# MCU.net
KiCad netlist of a schematic drawn in Altium Designer
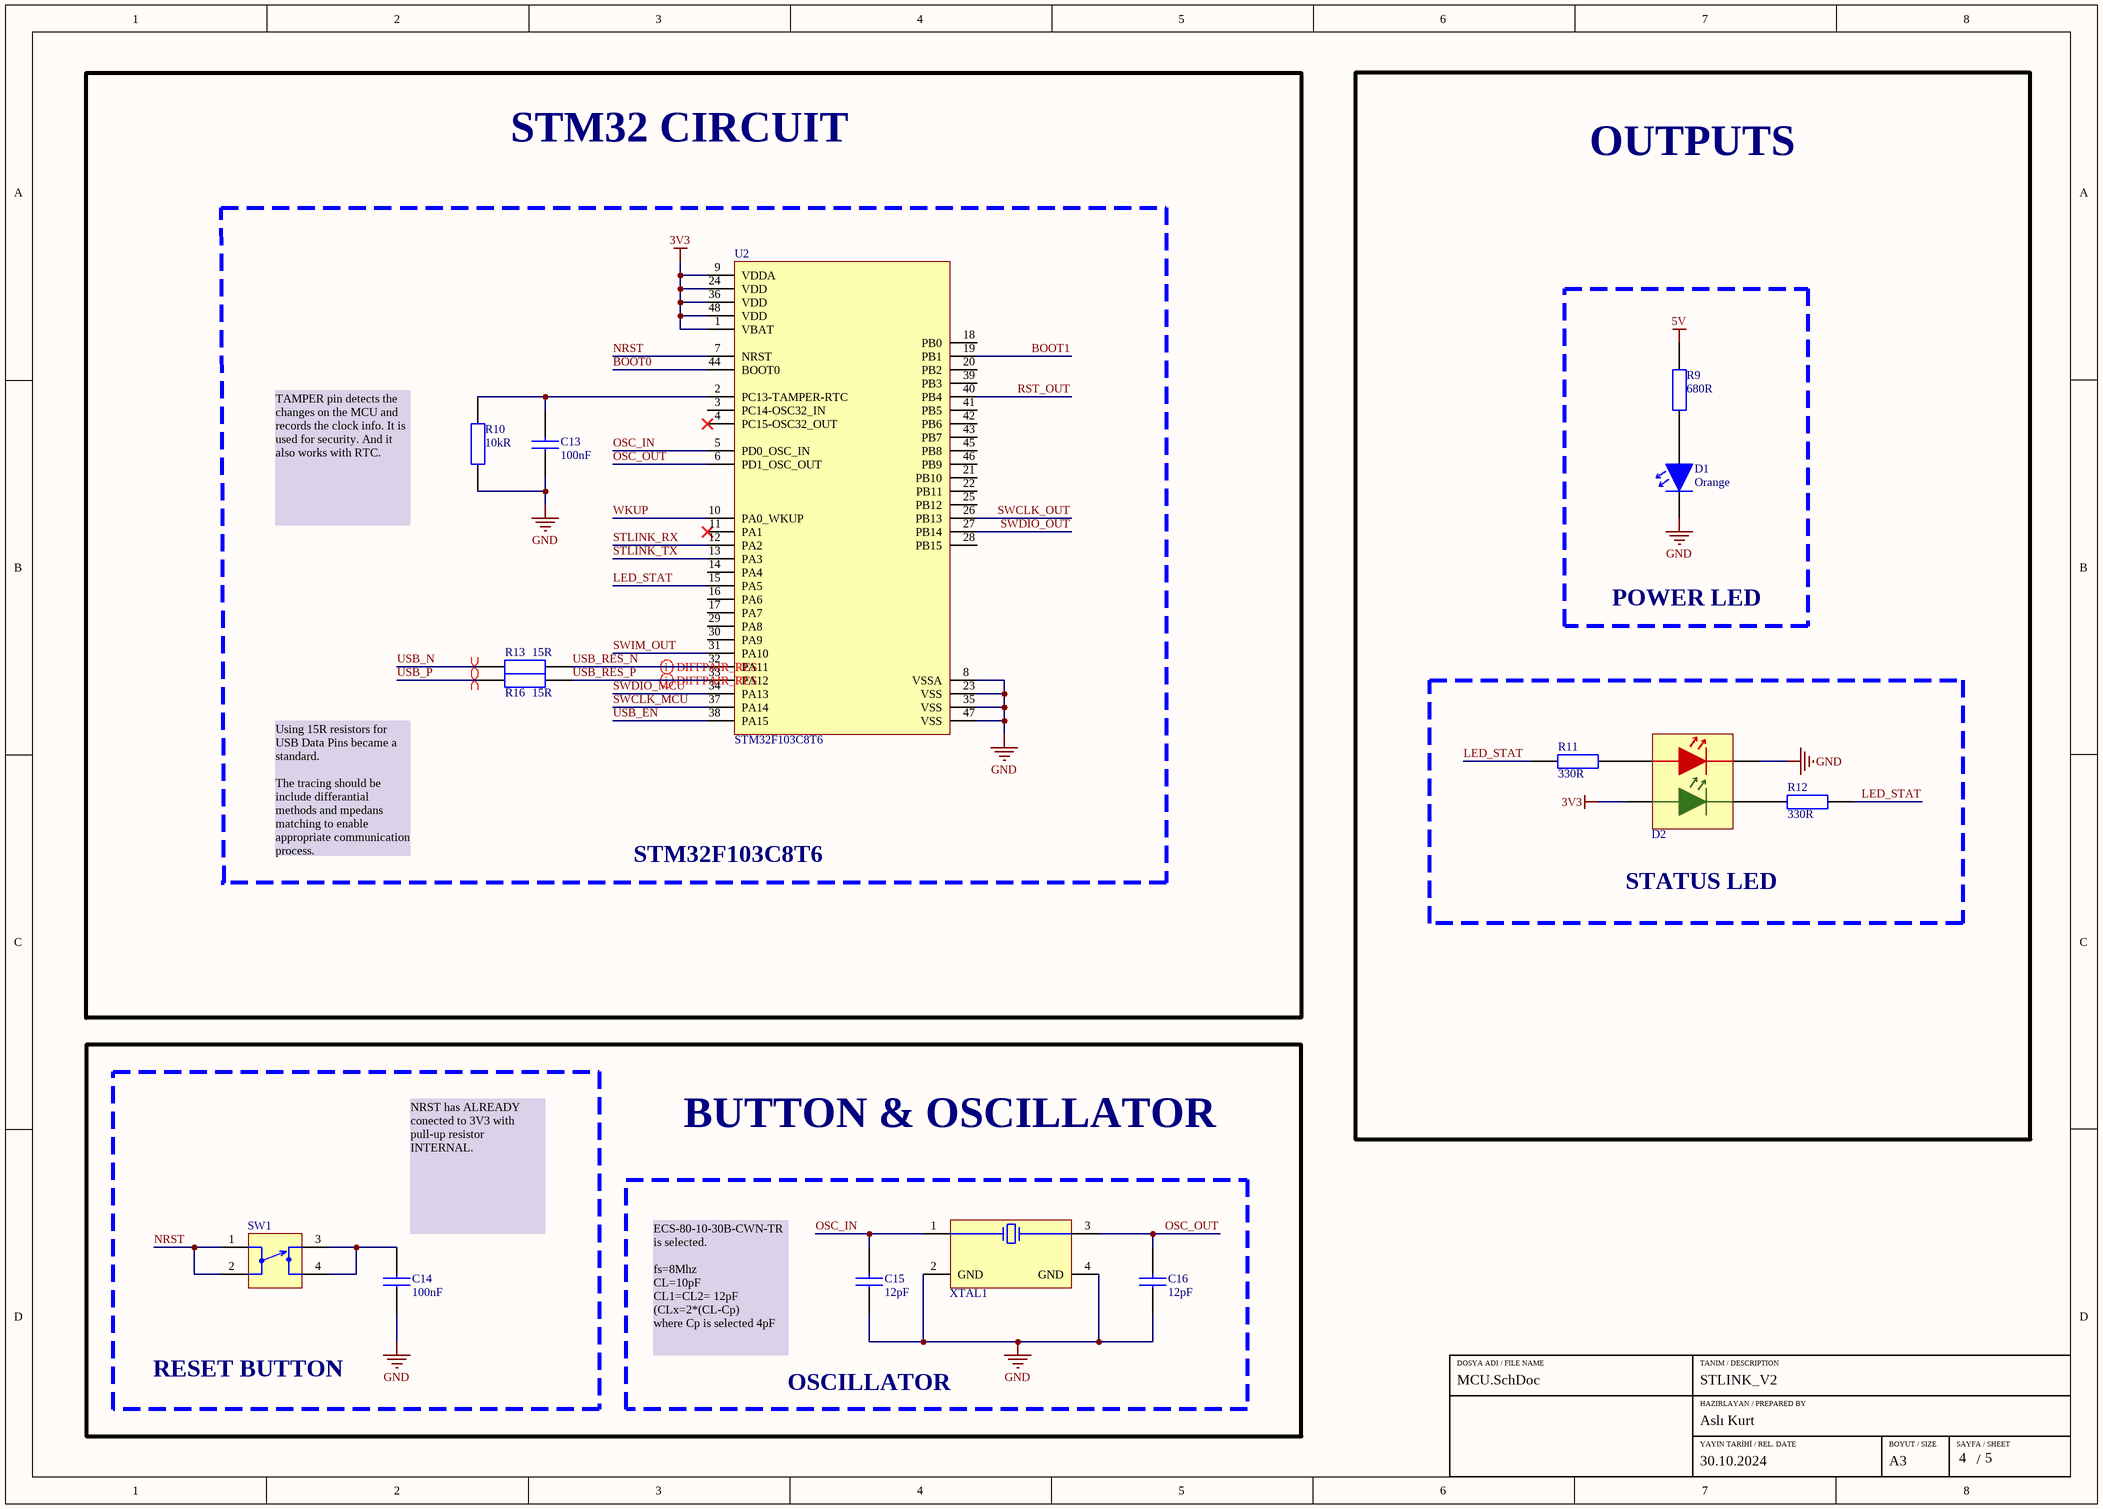
[diagram p0: MCU.SchDoc]

(export (version "E")
  (design (tool "Eeschema 10.0.6"))
  (components
    (comp (ref "C13")
      (value "C0603C104K5RACTU")
      (footprint "CAP_0603")
      (description "CAP CER 100nF %10 0603 SMD")
      (fields
        (field (name "MANUFACTURER") "KEMET")
        (field (name "TOLERANCE") "10%")
        (field (name "CAPACITANCE") "100nF")
        (field (name "DESIGNEDBY") "Aslı Kurt")
      )
      (libsource (lib "MyLibrary") (part "CAP CER 100nF 0603"))
    )
    (comp (ref "C14")
      (value "C0603C104K5RACTU")
      (footprint "CAP_0603")
      (description "CAP CER 100nF %10 0603 SMD")
      (fields
        (field (name "MANUFACTURER") "KEMET")
        (field (name "TOLERANCE") "10%")
        (field (name "CAPACITANCE") "100nF")
        (field (name "DESIGNEDBY") "Aslı Kurt")
      )
      (libsource (lib "MyLibrary") (part "CAP CER 100nF 0603"))
    )
    (comp (ref "C15")
      (value "CC0603FRNPO9BN120")
      (footprint "CAP_0603")
      (description "Multilayer Ceramic Capacitor, 12 pF, 50 V, ï¿½ 1%, C0G (NP0), 0603 [1608 Metric]")
      (fields
        (field (name "MANUFACTURER") "Yageo")
        (field (name "TOLERANCE") "1%")
        (field (name "CAPACITANCE") "12pF")
        (field (name "DESIGNEDBY") "Aslı Kurt")
      )
      (libsource (lib "MyLibrary") (part "CAP CER 12pF 0603"))
    )
    (comp (ref "C16")
      (value "CC0603FRNPO9BN120")
      (footprint "CAP_0603")
      (description "Multilayer Ceramic Capacitor, 12 pF, 50 V, ï¿½ 1%, C0G (NP0), 0603 [1608 Metric]")
      (fields
        (field (name "MANUFACTURER") "Yageo")
        (field (name "TOLERANCE") "1%")
        (field (name "CAPACITANCE") "12pF")
        (field (name "DESIGNEDBY") "Aslı Kurt")
      )
      (libsource (lib "MyLibrary") (part "CAP CER 12pF 0603"))
    )
    (comp (ref "D1")
      (value "LTST-C170KFKT")
      (footprint "LED_ORANGE_0805")
      (description "LED Uni-Color Orange 611nm 2-Pin Chip LED T/R / LED ORANGE CLEAR 0805 SMD")
      (fields
        (field (name "MANUFACTURER") "Vishay Lite-On")
        (field (name "ILLUMINATION COLOR") "Orange")
        (field (name "DESIGNEDBY") "Aslı Kurt")
      )
      (libsource (lib "MyLibrary") (part "LED ORANGE 0805"))
    )
    (comp (ref "D2")
      (value "APHB1608CGKSURKC")
      (footprint "LED_INDP_GREENRED_0603")
      (description "Green/Red 0603 130° Clear 50/250 mcd 2.1/1.95 V Surface Mount Flat Top LED")
      (fields (field (name "MANUFACTURER") "Kingbright"))
      (libsource (lib "MyLibrary") (part "LED_INDP_GREENRED_0603"))
    )
    (comp (ref "R9")
      (value "RC1206FR-07680RL")
      (footprint "RES_1206")
      (description "SMD Chip Resistor, 680 Ohm, ï¿½ 1%, 250 mW, 1206 [3216 Metric], Thick Film, General Purpose")
      (fields
        (field (name "MANUFACTURER") "Yageo")
        (field (name "RESISTANCE") "680R")
        (field (name "DESIGNEDBY") "Aslı Kurt")
      )
      (libsource (lib "MyLibrary") (part "RES 680 OHM 1206"))
    )
    (comp (ref "R10")
      (value "RC0603FR-0710KL")
      (footprint "RES_0603")
      (description "RES 10K %1 OHM 0603 SMD")
      (fields
        (field (name "MANUFACTURER") "Yageo")
        (field (name "TOLERANCE") "1%")
        (field (name "RESISTANCE") "10kR")
        (field (name "DESIGNEDBY") "Aslı Kurt")
      )
      (libsource (lib "MyLibrary") (part "RES 10K OHM 0603"))
    )
    (comp (ref "R11")
      (value "ERJ-H3EF3300V")
      (footprint "RES_0603")
      (description "RES, 330R, 1%, 0.125W, 0603;")
      (fields
        (field (name "MANUFACTURER") "Panasonic")
        (field (name "RESISTANCE") "330R")
        (field (name "DESIGNEDBY") "Aslı Kurt")
      )
      (libsource (lib "MyLibrary") (part "RES 330 OHM 0603"))
    )
    (comp (ref "R12")
      (value "ERJ-H3EF3300V")
      (footprint "RES_0603")
      (description "RES, 330R, 1%, 0.125W, 0603;")
      (fields
        (field (name "MANUFACTURER") "Panasonic")
        (field (name "RESISTANCE") "330R")
        (field (name "DESIGNEDBY") "Aslı Kurt")
      )
      (libsource (lib "MyLibrary") (part "RES 330 OHM 0603"))
    )
    (comp (ref "R13")
      (value "RC0603JR-0715RL")
      (footprint "RES_0603")
      (description "RES 15 %5 OHM 0603 SMD")
      (fields
        (field (name "MANUFACTURER") "Yageo")
        (field (name "TOLERANCE") "5%")
        (field (name "RESISTANCE") "15R")
        (field (name "DESIGNEDBY") "Aslı Kurt")
      )
      (libsource (lib "MyLibrary") (part "RES 15 OHM 0603"))
    )
    (comp (ref "R16")
      (value "RC0603JR-0715RL")
      (footprint "RES_0603")
      (description "RES 15 %5 OHM 0603 SMD")
      (fields
        (field (name "MANUFACTURER") "Yageo")
        (field (name "TOLERANCE") "5%")
        (field (name "RESISTANCE") "15R")
        (field (name "DESIGNEDBY") "Aslı Kurt")
      )
      (libsource (lib "MyLibrary") (part "RES 15 OHM 0603"))
    )
    (comp (ref "SW1")
      (value "PTS810 SJG 250 SMTR LFS")
      (footprint "BUTTON_SMD_BLUE")
      (description "Switch Tactile N.O. SPST Button J-Bend 0.05A 16VDC 100000Cycles 3.92N SMD T/R")
      (fields
        (field (name "MANUFACTURER") "ITT C&K")
        (field (name "MANUFACTURER PART NUMBER") "PTS810SJG250SMTRLFS")
        (field (name "DESIGNEDBY") "Aslı Kurt")
      )
      (libsource (lib "MyLibrary") (part "PTS810 SJG 250 SMTR LFS"))
    )
    (comp (ref "U2")
      (value "STM32F103C8T6")
      (footprint "LQFP48-STM")
      (description "ARM Cortex-M3 STM32 F1 Microcontroller 32-Bit 72MHz 64kB FLASH LQFP48 STM32F103C8T6")
      (fields (field (name "MANUFACTURER") "STMicroelectronics") (field (name "DESIGNEDBY") "Aslı Kurt"))
      (libsource (lib "MyLibrary") (part "STM32F103C8T6"))
    )
    (comp (ref "XTAL1")
      (value "ECS-80-10-30B-CWN-TR")
      (footprint "4-SMD, No Lead")
      (description "Crystal 8MHz ±10ppm (Tol) ±15ppm (Stability) 10pF FUND 100Ohm 4-Pin Mini-SMD T/R")
      (fields (field (name "MANUFACTURER") "ECS International") (field (name "DESIGNEDBY") "Aslı Kurt"))
      (libsource (lib "MyLibrary") (part "ECS-80-10-30B-CWN-TR"))
    )
  )
  (nets
    (net (code "1") (name "/BOOT0") (class "Default")
      (node (ref "U2") (pin "44") (pinfunction "BOOT0_44") (pintype "passive"))
    )
    (net (code "2") (name "/BOOT1") (class "Default")
      (node (ref "U2") (pin "19") (pinfunction "PB1_19") (pintype "passive"))
    )
    (net (code "3") (name "/LED_STAT") (class "Default")
      (node (ref "R11") (pin "1") (pinfunction "1_1") (pintype "passive"))
      (node (ref "R12") (pin "2") (pinfunction "2_2") (pintype "passive"))
      (node (ref "U2") (pin "15") (pinfunction "PA5_15") (pintype "passive"))
    )
    (net (code "4") (name "/NRST") (class "Default")
      (node (ref "SW1") (pin "1") (pinfunction "1_1") (pintype "passive"))
      (node (ref "SW1") (pin "2") (pinfunction "2_2") (pintype "passive"))
      (node (ref "U2") (pin "7") (pinfunction "NRST_7") (pintype "passive"))
    )
    (net (code "5") (name "/OSC_IN") (class "Default")
      (node (ref "C15") (pin "2") (pinfunction "2_2") (pintype "passive"))
      (node (ref "U2") (pin "5") (pinfunction "PD0_OSC_IN_5") (pintype "passive"))
      (node (ref "XTAL1") (pin "1") (pinfunction "1_1") (pintype "passive"))
    )
    (net (code "6") (name "/OSC_OUT") (class "Default")
      (node (ref "C16") (pin "2") (pinfunction "2_2") (pintype "passive"))
      (node (ref "U2") (pin "6") (pinfunction "PD1_OSC_OUT_6") (pintype "passive"))
      (node (ref "XTAL1") (pin "3") (pinfunction "3_3") (pintype "passive"))
    )
    (net (code "7") (name "/RST_OUT") (class "Default")
      (node (ref "U2") (pin "40") (pinfunction "PB4_40") (pintype "passive"))
    )
    (net (code "8") (name "/STLINK_RX") (class "Default")
      (node (ref "U2") (pin "12") (pinfunction "PA2_12") (pintype "passive"))
    )
    (net (code "9") (name "/STLINK_TX") (class "Default")
      (node (ref "U2") (pin "13") (pinfunction "PA3_13") (pintype "passive"))
    )
    (net (code "10") (name "/SWCLK_MCU") (class "Default")
      (node (ref "U2") (pin "37") (pinfunction "PA14_37") (pintype "passive"))
    )
    (net (code "11") (name "/SWCLK_OUT") (class "Default")
      (node (ref "U2") (pin "26") (pinfunction "PB13_26") (pintype "passive"))
    )
    (net (code "12") (name "/SWDIO_MCU") (class "Default")
      (node (ref "U2") (pin "34") (pinfunction "PA13_34") (pintype "passive"))
    )
    (net (code "13") (name "/SWDIO_OUT") (class "Default")
      (node (ref "U2") (pin "27") (pinfunction "PB14_27") (pintype "passive"))
    )
    (net (code "14") (name "/SWIM_OUT") (class "Default")
      (node (ref "U2") (pin "31") (pinfunction "PA10_31") (pintype "passive"))
    )
    (net (code "15") (name "/USB_EN") (class "Default")
      (node (ref "U2") (pin "38") (pinfunction "PA15_38") (pintype "passive"))
    )
    (net (code "16") (name "/USB_N") (class "Default")
      (node (ref "R13") (pin "1") (pinfunction "1_1") (pintype "passive"))
    )
    (net (code "17") (name "/USB_P") (class "Default")
      (node (ref "R16") (pin "1") (pinfunction "1_1") (pintype "passive"))
    )
    (net (code "18") (name "/USB_RES_N") (class "Default")
      (node (ref "R13") (pin "2") (pinfunction "2_2") (pintype "passive"))
      (node (ref "U2") (pin "32") (pinfunction "PA11_32") (pintype "passive"))
    )
    (net (code "19") (name "/USB_RES_P") (class "Default")
      (node (ref "R16") (pin "2") (pinfunction "2_2") (pintype "passive"))
      (node (ref "U2") (pin "33") (pinfunction "PA12_33") (pintype "passive"))
    )
    (net (code "20") (name "/WKUP") (class "Default")
      (node (ref "U2") (pin "10") (pinfunction "PA0_WKUP_10") (pintype "passive"))
    )
    (net (code "21") (name "3V3") (class "Default")
      (node (ref "D2") (pin "1") (pinfunction "1_1") (pintype "power_in"))
      (node (ref "U2") (pin "1") (pinfunction "VBAT_1") (pintype "passive"))
      (node (ref "U2") (pin "24") (pinfunction "VDD_24") (pintype "passive"))
      (node (ref "U2") (pin "36") (pinfunction "VDD_36") (pintype "passive"))
      (node (ref "U2") (pin "48") (pinfunction "VDD_48") (pintype "passive"))
      (node (ref "U2") (pin "9") (pinfunction "VDDA_9") (pintype "passive"))
    )
    (net (code "22") (name "5V") (class "Default")
      (node (ref "R9") (pin "1") (pinfunction "1_1") (pintype "passive"))
    )
    (net (code "23") (name "GND") (class "Default")
      (node (ref "C13") (pin "1") (pinfunction "1_1") (pintype "passive"))
      (node (ref "C14") (pin "1") (pinfunction "1_1") (pintype "passive"))
      (node (ref "C15") (pin "1") (pinfunction "1_1") (pintype "passive"))
      (node (ref "C16") (pin "1") (pinfunction "1_1") (pintype "passive"))
      (node (ref "D1") (pin "1") (pinfunction "1_1") (pintype "power_in"))
      (node (ref "D2") (pin "4") (pinfunction "4_4") (pintype "power_in"))
      (node (ref "R10") (pin "1") (pinfunction "1_1") (pintype "passive"))
      (node (ref "U2") (pin "23") (pinfunction "VSS_23") (pintype "passive"))
      (node (ref "U2") (pin "35") (pinfunction "VSS_35") (pintype "passive"))
      (node (ref "U2") (pin "47") (pinfunction "VSS_47") (pintype "passive"))
      (node (ref "U2") (pin "8") (pinfunction "VSSA_8") (pintype "passive"))
      (node (ref "XTAL1") (pin "2") (pinfunction "GND_2") (pintype "passive"))
      (node (ref "XTAL1") (pin "4") (pinfunction "GND_4") (pintype "passive"))
    )
    (net (code "24") (name "Net-(C14-Pad2)") (class "Default")
      (node (ref "C14") (pin "2") (pinfunction "2_2") (pintype "passive"))
      (node (ref "SW1") (pin "3") (pinfunction "3_3") (pintype "passive"))
      (node (ref "SW1") (pin "4") (pinfunction "4_4") (pintype "passive"))
    )
    (net (code "25") (name "Net-(D1-Pad2)") (class "Default")
      (node (ref "D1") (pin "2") (pinfunction "2_2") (pintype "power_in"))
      (node (ref "R9") (pin "2") (pinfunction "2_2") (pintype "passive"))
    )
    (net (code "26") (name "Net-(D2-Pad2)") (class "Default")
      (node (ref "D2") (pin "2") (pinfunction "2_2") (pintype "power_in"))
      (node (ref "R12") (pin "1") (pinfunction "1_1") (pintype "passive"))
    )
    (net (code "27") (name "Net-(D2-Pad3)") (class "Default")
      (node (ref "D2") (pin "3") (pinfunction "3_3") (pintype "power_in"))
      (node (ref "R11") (pin "2") (pinfunction "2_2") (pintype "passive"))
    )
    (net (code "28") (name "Net-(U2-PC13-TAMPER-RTC)") (class "Default")
      (node (ref "C13") (pin "2") (pinfunction "2_2") (pintype "passive"))
      (node (ref "R10") (pin "2") (pinfunction "2_2") (pintype "passive"))
      (node (ref "U2") (pin "2") (pinfunction "PC13-TAMPER-RTC_2") (pintype "passive"))
    )
    (net (code "29") (name "unconnected-(U2-PA1-Pad11)") (class "Default")
      (node (ref "U2") (pin "11") (pinfunction "PA1_11") (pintype "passive+no_connect"))
    )
    (net (code "30") (name "unconnected-(U2-PA4-Pad14)") (class "Default")
      (node (ref "U2") (pin "14") (pinfunction "PA4_14") (pintype "passive"))
    )
    (net (code "31") (name "unconnected-(U2-PA6-Pad16)") (class "Default")
      (node (ref "U2") (pin "16") (pinfunction "PA6_16") (pintype "passive"))
    )
    (net (code "32") (name "unconnected-(U2-PA7-Pad17)") (class "Default")
      (node (ref "U2") (pin "17") (pinfunction "PA7_17") (pintype "passive"))
    )
    (net (code "33") (name "unconnected-(U2-PA8-Pad29)") (class "Default")
      (node (ref "U2") (pin "29") (pinfunction "PA8_29") (pintype "passive"))
    )
    (net (code "34") (name "unconnected-(U2-PA9-Pad30)") (class "Default")
      (node (ref "U2") (pin "30") (pinfunction "PA9_30") (pintype "passive"))
    )
    (net (code "35") (name "unconnected-(U2-PB0-Pad18)") (class "Default")
      (node (ref "U2") (pin "18") (pinfunction "PB0_18") (pintype "passive"))
    )
    (net (code "36") (name "unconnected-(U2-PB2-Pad20)") (class "Default")
      (node (ref "U2") (pin "20") (pinfunction "PB2_20") (pintype "passive"))
    )
    (net (code "37") (name "unconnected-(U2-PB3-Pad39)") (class "Default")
      (node (ref "U2") (pin "39") (pinfunction "PB3_39") (pintype "passive"))
    )
    (net (code "38") (name "unconnected-(U2-PB5-Pad41)") (class "Default")
      (node (ref "U2") (pin "41") (pinfunction "PB5_41") (pintype "passive"))
    )
    (net (code "39") (name "unconnected-(U2-PB6-Pad42)") (class "Default")
      (node (ref "U2") (pin "42") (pinfunction "PB6_42") (pintype "passive"))
    )
    (net (code "40") (name "unconnected-(U2-PB7-Pad43)") (class "Default")
      (node (ref "U2") (pin "43") (pinfunction "PB7_43") (pintype "passive"))
    )
    (net (code "41") (name "unconnected-(U2-PB8-Pad45)") (class "Default")
      (node (ref "U2") (pin "45") (pinfunction "PB8_45") (pintype "passive"))
    )
    (net (code "42") (name "unconnected-(U2-PB9-Pad46)") (class "Default")
      (node (ref "U2") (pin "46") (pinfunction "PB9_46") (pintype "passive"))
    )
    (net (code "43") (name "unconnected-(U2-PB10-Pad21)") (class "Default")
      (node (ref "U2") (pin "21") (pinfunction "PB10_21") (pintype "passive"))
    )
    (net (code "44") (name "unconnected-(U2-PB11-Pad22)") (class "Default")
      (node (ref "U2") (pin "22") (pinfunction "PB11_22") (pintype "passive"))
    )
    (net (code "45") (name "unconnected-(U2-PB12-Pad25)") (class "Default")
      (node (ref "U2") (pin "25") (pinfunction "PB12_25") (pintype "passive"))
    )
    (net (code "46") (name "unconnected-(U2-PB15-Pad28)") (class "Default")
      (node (ref "U2") (pin "28") (pinfunction "PB15_28") (pintype "passive"))
    )
    (net (code "47") (name "unconnected-(U2-PC14-OSC32_IN-Pad3)") (class "Default")
      (node (ref "U2") (pin "3") (pinfunction "PC14-OSC32_IN_3") (pintype "passive"))
    )
    (net (code "48") (name "unconnected-(U2-PC15-OSC32_OUT-Pad4)") (class "Default")
      (node (ref "U2") (pin "4") (pinfunction "PC15-OSC32_OUT_4") (pintype "passive+no_connect"))
    )
  )
)
